# LiquorLight.net
KiCad netlist of a schematic drawn in EAGLE
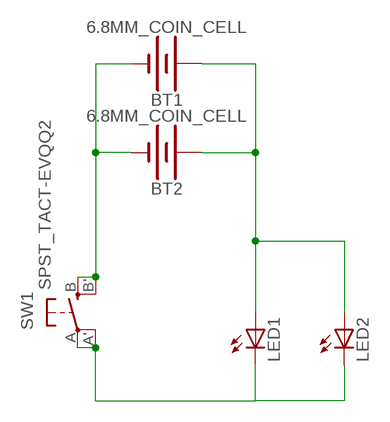
[diagram p0: schematic, sheet 1]

(export (version "E")
  (design (tool "Eeschema 10.0.6"))
  (components
    (comp (ref "BT1")
      (value "6.8MM_COIN_CELL")
      (footprint "eagle-import:BATTCON-6.8MM")
      (libsource (lib "eagle-import") (part "BATTERY-6.8MM_SMD"))
    )
    (comp (ref "BT2")
      (value "6.8MM_COIN_CELL")
      (footprint "eagle-import:BATTCON-6.8MM")
      (libsource (lib "eagle-import") (part "BATTERY-6.8MM_SMD"))
    )
    (comp (ref "LED1")
      (value "LED3MM")
      (footprint "eagle-import:LED3MM")
      (libsource (lib "eagle-import") (part "LED3MM"))
    )
    (comp (ref "LED2")
      (value "LED3MM")
      (footprint "eagle-import:LED3MM")
      (libsource (lib "eagle-import") (part "LED3MM"))
    )
    (comp (ref "SW1")
      (value "SPST_TACT-EVQQ2")
      (footprint "eagle-import:EVQ-Q2")
      (libsource (lib "eagle-import") (part "SPST_TACT-EVQQ2"))
    )
  )
  (nets
    (net (code "1") (name "Net-(BT1-Pad+)") (class "Default")
      (node (ref "BT1") (pin "+") (pinfunction "+_+") (pintype "power_in"))
      (node (ref "BT2") (pin "+") (pinfunction "+_+") (pintype "power_in"))
      (node (ref "LED1") (pin "A") (pinfunction "A_A") (pintype "passive"))
      (node (ref "LED2") (pin "A") (pinfunction "A_A") (pintype "passive"))
    )
    (net (code "2") (name "Net-(LED1-C)") (class "Default")
      (node (ref "LED1") (pin "K") (pinfunction "C_K") (pintype "passive"))
      (node (ref "LED2") (pin "K") (pinfunction "C_K") (pintype "passive"))
      (node (ref "SW1") (pin "A") (pinfunction "P_A") (pintype "passive"))
      (node (ref "SW1") (pin "A'") (pinfunction "P1_A'") (pintype "passive"))
    )
    (net (code "3") (name "Net-(SW1-S)") (class "Default")
      (node (ref "BT1") (pin "-") (pinfunction "-_-") (pintype "power_in"))
      (node (ref "BT2") (pin "-") (pinfunction "-_-") (pintype "power_in"))
      (node (ref "SW1") (pin "B") (pinfunction "S_B") (pintype "passive"))
      (node (ref "SW1") (pin "B'") (pinfunction "S1_B'") (pintype "passive"))
    )
  )
)
